# Sheet1.net
KiCad netlist of a schematic drawn in Altium Designer
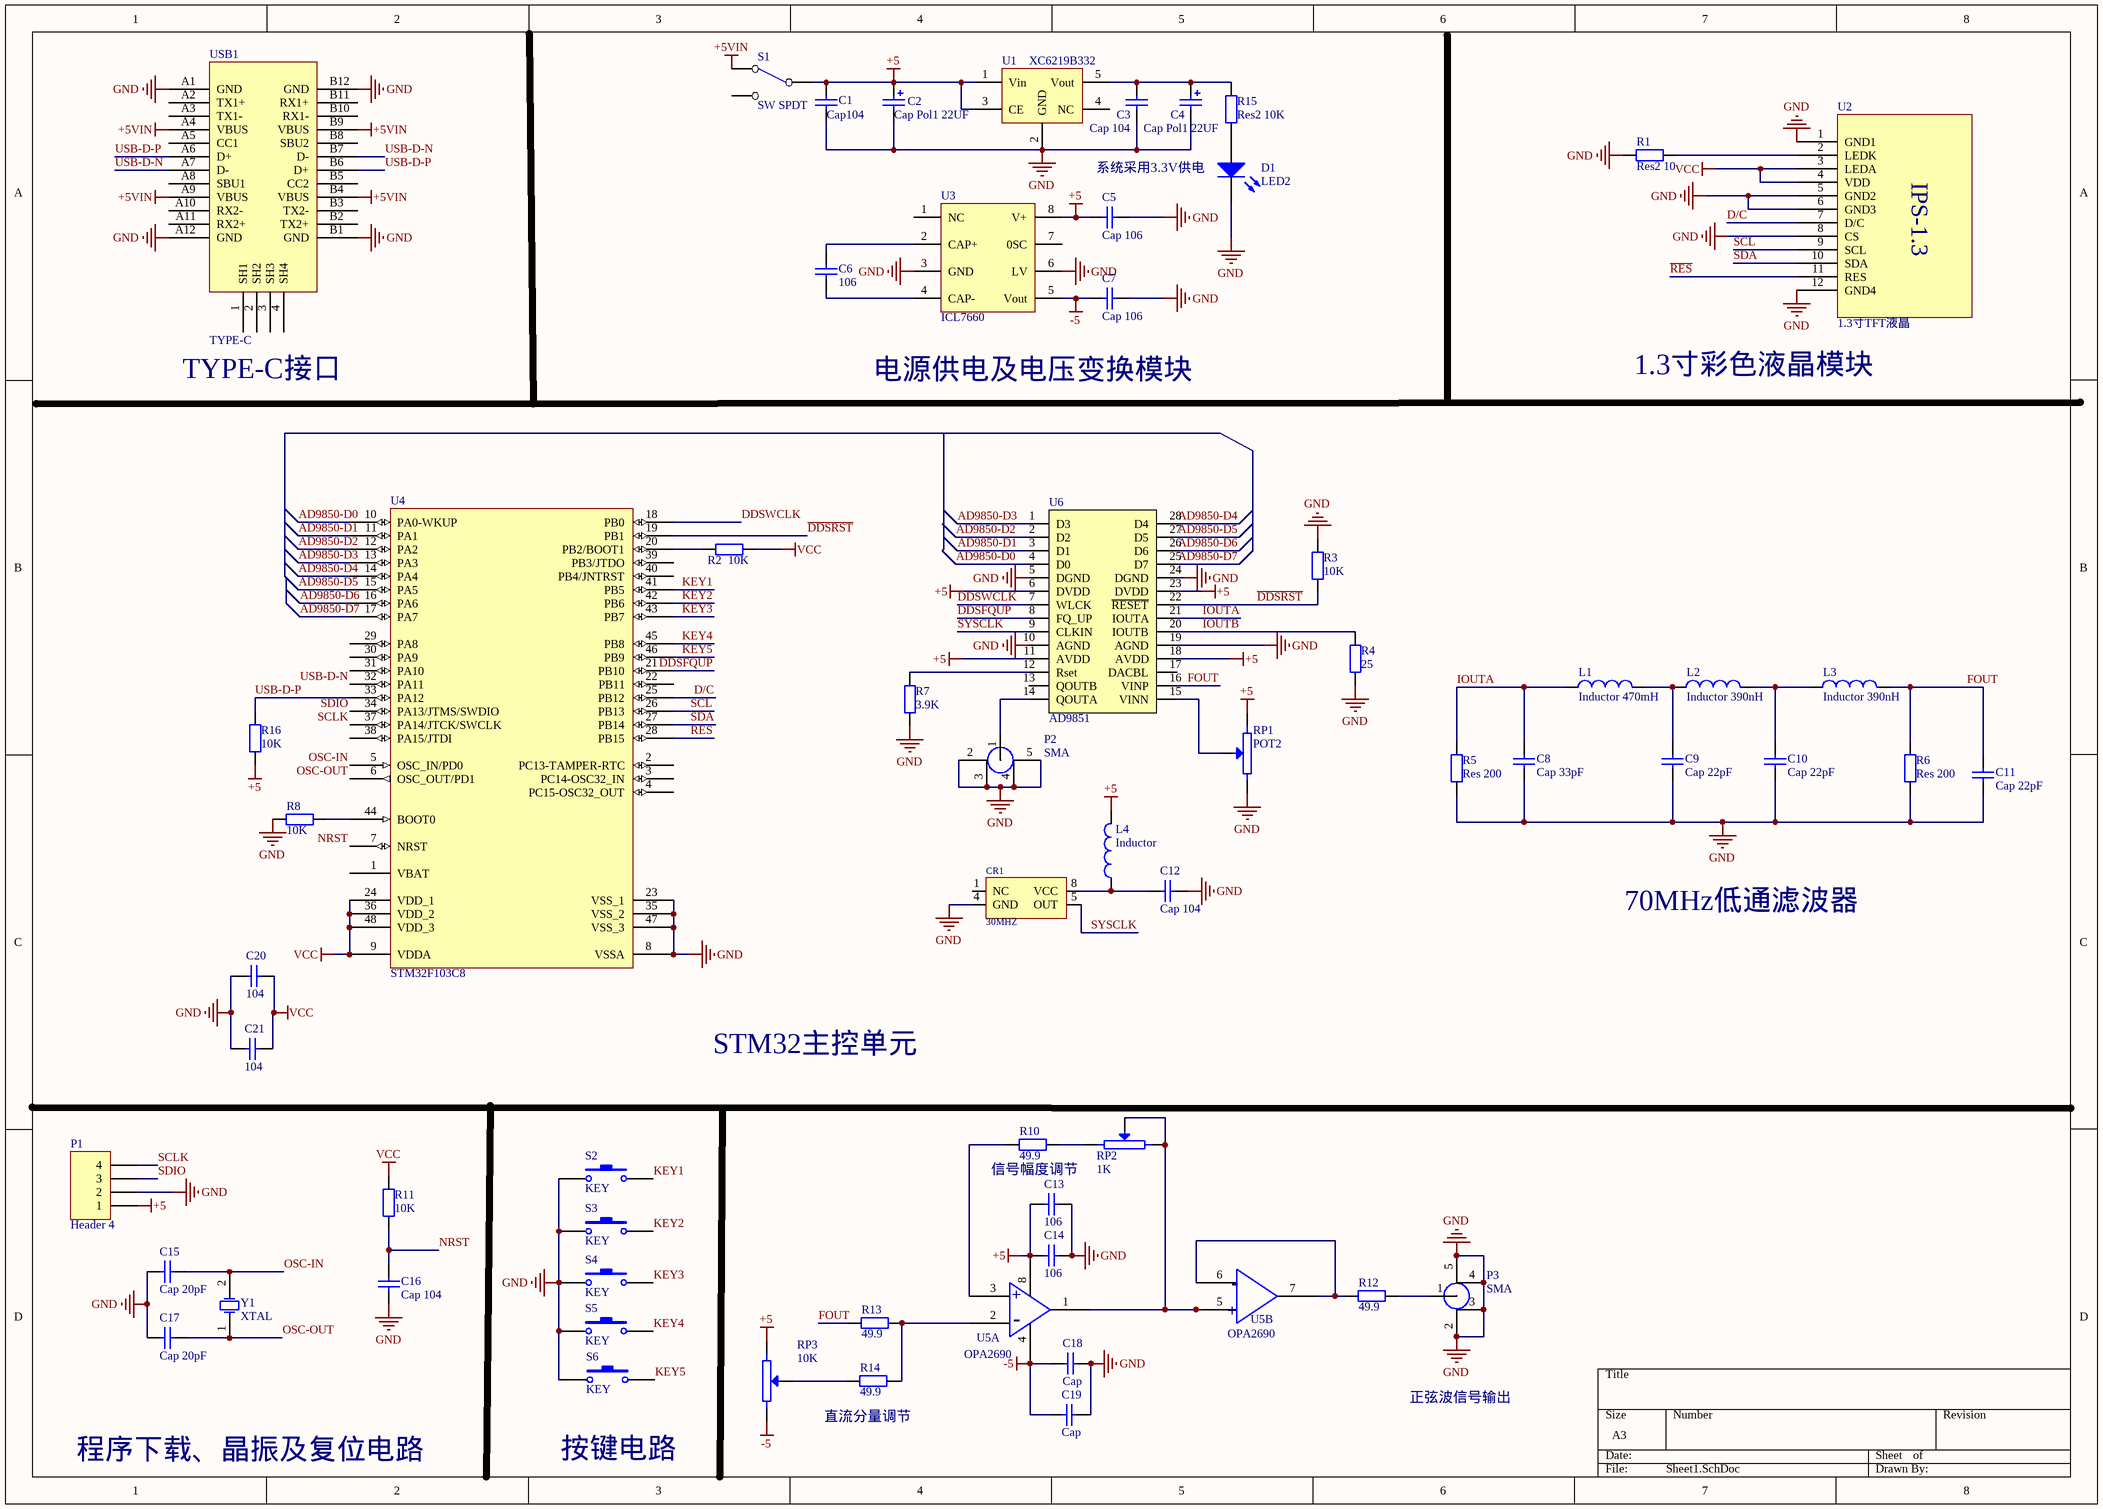
[diagram p0: Sheet1.SchDoc]

(export (version "E")
  (design (tool "Eeschema 10.0.6"))
  (components
    (comp (ref "C1")
      (value "Cap104")
      (footprint "C0805")
      (description "Capacitor")
      (fields (field (name "PUBLISHER") "Altium Limited"))
      (libsource (lib "基于STM32的DDS信号源设计实例") (part "Cap"))
    )
    (comp (ref "C2")
      (value "Cap Pol1 22UF")
      (footprint "C1210_N")
      (description "Polarized Capacitor (Radial)")
      (fields (field (name "PUBLISHER") "Altium Limited"))
      (libsource (lib "基于STM32的DDS信号源设计实例") (part "Cap Pol1"))
    )
    (comp (ref "C3")
      (value "Cap 104")
      (footprint "C0805")
      (description "Capacitor")
      (fields (field (name "PUBLISHER") "Altium Limited"))
      (libsource (lib "基于STM32的DDS信号源设计实例") (part "Cap"))
    )
    (comp (ref "C4")
      (value "Cap Pol1 22UF")
      (footprint "C1210_N")
      (description "Polarized Capacitor (Radial)")
      (fields (field (name "PUBLISHER") "Altium Limited"))
      (libsource (lib "基于STM32的DDS信号源设计实例") (part "Cap Pol1"))
    )
    (comp (ref "C5")
      (value "Cap 106")
      (footprint "C0805")
      (description "106")
      (fields (field (name "PUBLISHER") "Altium Limited"))
      (libsource (lib "基于STM32的DDS信号源设计实例") (part "Cap"))
    )
    (comp (ref "C6")
      (value "106")
      (footprint "C0805")
      (description "Capacitor")
      (fields (field (name "PUBLISHER") "Altium Limited"))
      (libsource (lib "基于STM32的DDS信号源设计实例") (part "Cap"))
    )
    (comp (ref "C7")
      (value "Cap 106")
      (footprint "C0805")
      (description "Capacitor")
      (fields (field (name "PUBLISHER") "Altium Limited"))
      (libsource (lib "基于STM32的DDS信号源设计实例") (part "Cap"))
    )
    (comp (ref "C8")
      (value "Cap 33pF")
      (footprint "C0805")
      (description "Capacitor")
      (fields (field (name "PUBLISHER") "Altium Limited"))
      (libsource (lib "基于STM32的DDS信号源设计实例") (part "Cap"))
    )
    (comp (ref "C9")
      (value "Cap 22pF")
      (footprint "C0805")
      (description "Capacitor")
      (fields (field (name "PUBLISHER") "Altium Limited"))
      (libsource (lib "基于STM32的DDS信号源设计实例") (part "Cap"))
    )
    (comp (ref "C10")
      (value "Cap 22pF")
      (footprint "C0805")
      (description "Capacitor")
      (fields (field (name "PUBLISHER") "Altium Limited"))
      (libsource (lib "基于STM32的DDS信号源设计实例") (part "Cap"))
    )
    (comp (ref "C11")
      (value "Cap 22pF")
      (footprint "C0805")
      (description "Capacitor")
      (fields (field (name "PUBLISHER") "Altium Limited"))
      (libsource (lib "基于STM32的DDS信号源设计实例") (part "Cap"))
    )
    (comp (ref "C12")
      (value "Cap 104")
      (footprint "C0805")
      (description "Capacitor")
      (fields (field (name "PUBLISHER") "Altium Limited"))
      (libsource (lib "基于STM32的DDS信号源设计实例") (part "Cap"))
    )
    (comp (ref "C13")
      (value "106")
      (footprint "C0805")
      (description "Capacitor")
      (fields (field (name "PUBLISHER") "Altium Limited"))
      (libsource (lib "基于STM32的DDS信号源设计实例") (part "Cap"))
    )
    (comp (ref "C14")
      (value "106")
      (footprint "C0805")
      (description "Capacitor")
      (fields (field (name "PUBLISHER") "Altium Limited"))
      (libsource (lib "基于STM32的DDS信号源设计实例") (part "Cap"))
    )
    (comp (ref "C15")
      (value "Cap 20pF")
      (footprint "C0805")
      (description "Capacitor")
      (fields (field (name "PUBLISHER") "Altium Limited"))
      (libsource (lib "基于STM32的DDS信号源设计实例") (part "Cap"))
    )
    (comp (ref "C16")
      (value "Cap 104")
      (footprint "C0805")
      (description "Capacitor")
      (fields (field (name "PUBLISHER") "Altium Limited"))
      (libsource (lib "基于STM32的DDS信号源设计实例") (part "Cap"))
    )
    (comp (ref "C17")
      (value "Cap 20pF")
      (footprint "C0805")
      (description "Capacitor")
      (fields (field (name "PUBLISHER") "Altium Limited"))
      (libsource (lib "基于STM32的DDS信号源设计实例") (part "Cap"))
    )
    (comp (ref "C18")
      (value "Cap")
      (footprint "C0805")
      (description "Capacitor")
      (fields (field (name "PUBLISHER") "Altium Limited"))
      (libsource (lib "基于STM32的DDS信号源设计实例") (part "Cap"))
    )
    (comp (ref "C19")
      (value "Cap")
      (footprint "C0805")
      (description "Capacitor")
      (fields (field (name "PUBLISHER") "Altium Limited"))
      (libsource (lib "基于STM32的DDS信号源设计实例") (part "Cap"))
    )
    (comp (ref "C20")
      (value "104")
      (footprint "C0805")
      (description "Capacitor")
      (fields (field (name "PUBLISHER") "Altium Limited"))
      (libsource (lib "基于STM32的DDS信号源设计实例") (part "Cap"))
    )
    (comp (ref "C21")
      (value "104")
      (footprint "C0805")
      (description "Capacitor")
      (fields (field (name "PUBLISHER") "Altium Limited"))
      (libsource (lib "基于STM32的DDS信号源设计实例") (part "Cap"))
    )
    (comp (ref "CR1")
      (value "30MHZ")
      (footprint "CRYSTAL-SMT-5X7")
      (libsource (lib "基于STM32的DDS信号源设计实例") (part "CRYSTAL-DIP8"))
    )
    (comp (ref "D1")
      (value "LED2")
      (footprint "D0805+")
      (description "Typical RED, GREEN, YELLOW, AMBER GaAs LED")
      (fields (field (name "PUBLISHER") "Altium Limited"))
      (libsource (lib "基于STM32的DDS信号源设计实例") (part "LED2"))
    )
    (comp (ref "L1")
      (value "Inductor 470mH")
      (footprint "6-0805_N")
      (description "Inductor")
      (fields (field (name "PUBLISHER") "Altium Limited"))
      (libsource (lib "基于STM32的DDS信号源设计实例") (part "Inductor"))
    )
    (comp (ref "L2")
      (value "Inductor 390nH")
      (footprint "6-0805_N")
      (description "Inductor")
      (fields (field (name "PUBLISHER") "Altium Limited"))
      (libsource (lib "基于STM32的DDS信号源设计实例") (part "Inductor"))
    )
    (comp (ref "L3")
      (value "Inductor 390nH")
      (footprint "6-0805_N")
      (description "Inductor")
      (fields (field (name "PUBLISHER") "Altium Limited"))
      (libsource (lib "基于STM32的DDS信号源设计实例") (part "Inductor"))
    )
    (comp (ref "L4")
      (value "Inductor")
      (footprint "6-0805_N")
      (fields (field (name "PUBLISHER") "Altium Limited"))
      (libsource (lib "基于STM32的DDS信号源设计实例") (part "Inductor"))
    )
    (comp (ref "P1")
      (value "Header 4")
      (footprint "HDR1X4")
      (description "Header, 4-Pin")
      (fields (field (name "PUBLISHER") "Altium Limited"))
      (libsource (lib "基于STM32的DDS信号源设计实例") (part "Header 4"))
    )
    (comp (ref "P2") (value "SMA") (footprint "SMA-KE") (libsource (lib "Schlib1") (part "SMA")))
    (comp (ref "P3") (value "SMA") (footprint "SMA-KE") (libsource (lib "Schlib1") (part "SMA")))
    (comp (ref "R1")
      (value "Res2 10")
      (footprint "6-0805_N")
      (description "Resistor")
      (fields (field (name "PUBLISHER") "Altium Limited"))
      (libsource (lib "") (part "Res2_1"))
    )
    (comp (ref "R2")
      (value "10K")
      (footprint "6-0805_N")
      (description "Resistor")
      (fields (field (name "PUBLISHER") "Altium Limited"))
      (libsource (lib "") (part "Res2_1"))
    )
    (comp (ref "R3")
      (value "10K")
      (footprint "6-0805_N")
      (description "Resistor")
      (fields (field (name "PUBLISHER") "Altium Limited"))
      (libsource (lib "基于STM32的DDS信号源设计实例") (part "Res2"))
    )
    (comp (ref "R4")
      (value "25")
      (footprint "6-0805_N")
      (description "Resistor")
      (fields (field (name "PUBLISHER") "Altium Limited"))
      (libsource (lib "基于STM32的DDS信号源设计实例") (part "Res2"))
    )
    (comp (ref "R5")
      (value "Res 200")
      (footprint "6-0805_N")
      (description "Resistor")
      (fields (field (name "PUBLISHER") "Altium Limited"))
      (libsource (lib "基于STM32的DDS信号源设计实例") (part "Res2"))
    )
    (comp (ref "R6")
      (value "Res 200")
      (footprint "6-0805_N")
      (description "Resistor")
      (fields (field (name "PUBLISHER") "Altium Limited"))
      (libsource (lib "基于STM32的DDS信号源设计实例") (part "Res2"))
    )
    (comp (ref "R7")
      (value "3.9K")
      (footprint "6-0805_N")
      (description "Resistor")
      (fields (field (name "PUBLISHER") "Altium Limited"))
      (libsource (lib "基于STM32的DDS信号源设计实例") (part "Res2"))
    )
    (comp (ref "R8")
      (value "10K")
      (footprint "6-0805_N")
      (description "Resistor")
      (fields (field (name "PUBLISHER") "Altium Limited"))
      (libsource (lib "") (part "Res2_1"))
    )
    (comp (ref "R10")
      (value "49.9")
      (footprint "6-0805_N")
      (description "Resistor")
      (fields (field (name "PUBLISHER") "Altium Limited"))
      (libsource (lib "") (part "Res2_1"))
    )
    (comp (ref "R11")
      (value "10K")
      (footprint "6-0805_N")
      (description "Resistor")
      (fields (field (name "PUBLISHER") "Altium Limited"))
      (libsource (lib "基于STM32的DDS信号源设计实例") (part "Res2"))
    )
    (comp (ref "R12")
      (value "49.9")
      (footprint "6-0805_N")
      (description "Resistor")
      (fields (field (name "PUBLISHER") "Altium Limited"))
      (libsource (lib "") (part "Res2_1"))
    )
    (comp (ref "R13")
      (value "49.9")
      (footprint "6-0805_N")
      (description "Resistor")
      (fields (field (name "PUBLISHER") "Altium Limited"))
      (libsource (lib "") (part "Res2_1"))
    )
    (comp (ref "R14")
      (value "49.9")
      (footprint "6-0805_N")
      (description "Resistor")
      (fields (field (name "PUBLISHER") "Altium Limited"))
      (libsource (lib "") (part "Res2_1"))
    )
    (comp (ref "R15")
      (value "Res2 10K")
      (footprint "6-0805_N")
      (description "Resistor")
      (fields (field (name "PUBLISHER") "Altium Limited"))
      (libsource (lib "基于STM32的DDS信号源设计实例") (part "Res2"))
    )
    (comp (ref "R16")
      (value "10K")
      (footprint "6-0805_N")
      (description "Resistor")
      (fields (field (name "PUBLISHER") "Altium Limited"))
      (libsource (lib "基于STM32的DDS信号源设计实例") (part "Res2"))
    )
    (comp (ref "RP1")
      (value "POT2")
      (footprint "VR7")
      (description "Potentiometer")
      (libsource (lib "基于STM32的DDS信号源设计实例") (part "POT2"))
    )
    (comp (ref "RP2")
      (value "1K")
      (footprint "VR7")
      (description "Potentiometer")
      (libsource (lib "基于STM32的DDS信号源设计实例") (part "POT2"))
    )
    (comp (ref "RP3")
      (value "10K")
      (footprint "VR7")
      (description "Potentiometer")
      (libsource (lib "基于STM32的DDS信号源设计实例") (part "POT2"))
    )
    (comp (ref "S1")
      (value "SW SPDT")
      (footprint "SW-SPDT-7P")
      (libsource (lib "基于STM32的DDS信号源设计实例") (part "SW SPDT"))
    )
    (comp (ref "S2")
      (value "KEY")
      (footprint "SW-MINI")
      (description "Switch")
      (fields (field (name "PUBLISHER") "Altium Limited"))
      (libsource (lib "基于STM32的DDS信号源设计实例") (part "SW-PB"))
    )
    (comp (ref "S3")
      (value "KEY")
      (footprint "SW-MINI")
      (description "Switch")
      (fields (field (name "PUBLISHER") "Altium Limited"))
      (libsource (lib "基于STM32的DDS信号源设计实例") (part "SW-PB"))
    )
    (comp (ref "S4")
      (value "KEY")
      (footprint "SW-MINI")
      (description "Switch")
      (fields (field (name "PUBLISHER") "Altium Limited"))
      (libsource (lib "基于STM32的DDS信号源设计实例") (part "SW-PB"))
    )
    (comp (ref "S5")
      (value "KEY")
      (footprint "SW-MINI")
      (description "Switch")
      (fields (field (name "PUBLISHER") "Altium Limited"))
      (libsource (lib "基于STM32的DDS信号源设计实例") (part "SW-PB"))
    )
    (comp (ref "S6")
      (value "KEY")
      (footprint "SW-MINI")
      (description "Switch")
      (fields (field (name "PUBLISHER") "Altium Limited"))
      (libsource (lib "基于STM32的DDS信号源设计实例") (part "SW-PB"))
    )
    (comp (ref "U1")
      (value "XC6219B332")
      (footprint "SOT23-5L")
      (libsource (lib "基于STM32的DDS信号源设计实例") (part "XC6219"))
    )
    (comp (ref "U2")
      (value "1.3寸TFT液晶")
      (footprint "1.3-TFT-TPS")
      (libsource (lib "基于STM32的DDS信号源设计实例") (part "1.3寸TFT液晶"))
    )
    (comp (ref "U3")
      (value "ICL7660")
      (footprint "SO8_N")
      (libsource (lib "基于STM32的DDS信号源设计实例") (part "ICL7660"))
    )
    (comp (ref "U4")
      (value "STM32F103C8")
      (footprint "TQFP-48")
      (description "Flaah:64/RAM:20/IO:36")
      (fields (field (name "版权归属") "源创客"))
      (libsource (lib "基于STM32的DDS信号源设计实例") (part "STM32F103C8"))
    )
    (comp (ref "U5") (value "OPA2690") (footprint "SO-8") (libsource (lib "Schlib1") (part "OPA2690")))
    (comp (ref "U6") (value "AD9851") (footprint "TSSOP28") (libsource (lib "Schlib1") (part "AD9851")))
    (comp (ref "USB1")
      (value "TYPE-C")
      (footprint "TYPE-C")
      (libsource (lib "基于STM32的DDS信号源设计实例") (part "TYPE-C"))
    )
    (comp (ref "Y1")
      (value "XTAL")
      (footprint "XTAL2")
      (description "Crystal Oscillator")
      (fields (field (name "PUBLISHER") "Altium Limited"))
      (libsource (lib "基于STM32的DDS信号源设计实例") (part "XTAL"))
    )
  )
  (nets
    (net (code "1") (name "+5") (class "Default")
      (node (ref "C1") (pin "2") (pinfunction "2_2") (pintype "passive"))
      (node (ref "C13") (pin "1") (pinfunction "1_1") (pintype "passive"))
      (node (ref "C14") (pin "1") (pinfunction "1_1") (pintype "passive"))
      (node (ref "C2") (pin "1") (pinfunction "1_1") (pintype "passive"))
      (node (ref "C5") (pin "2") (pinfunction "2_2") (pintype "passive"))
      (node (ref "L4") (pin "2") (pinfunction "2_2") (pintype "passive"))
      (node (ref "P1") (pin "1") (pinfunction "1_1") (pintype "passive"))
      (node (ref "R16") (pin "1") (pinfunction "1_1") (pintype "passive"))
      (node (ref "RP1") (pin "2") (pinfunction "2_2") (pintype "passive"))
      (node (ref "RP3") (pin "1") (pinfunction "1_1") (pintype "passive"))
      (node (ref "S1") (pin "2") (pinfunction "COMMON_2") (pintype "passive"))
      (node (ref "U1") (pin "1") (pinfunction "Vin_1") (pintype "passive"))
      (node (ref "U1") (pin "3") (pinfunction "CE_3") (pintype "passive"))
      (node (ref "U3") (pin "8") (pinfunction "V+_8") (pintype "passive"))
      (node (ref "U5") (pin "8") (pintype "passive"))
      (node (ref "U6") (pin "11") (pinfunction "AVDD_11") (pintype "passive"))
      (node (ref "U6") (pin "18") (pinfunction "AVDD_18") (pintype "passive"))
      (node (ref "U6") (pin "23") (pinfunction "DVDD_23") (pintype "passive"))
      (node (ref "U6") (pin "6") (pinfunction "DVDD_6") (pintype "passive"))
    )
    (net (code "2") (name "+5VIN") (class "Default")
      (node (ref "S1") (pin "1") (pinfunction "NC_1") (pintype "passive"))
      (node (ref "USB1") (pin "A4") (pinfunction "VBUS_A4") (pintype "passive"))
      (node (ref "USB1") (pin "A9") (pinfunction "VBUS_A9") (pintype "passive"))
      (node (ref "USB1") (pin "B4") (pinfunction "VBUS_B4") (pintype "passive"))
      (node (ref "USB1") (pin "B9") (pinfunction "VBUS_B9") (pintype "passive"))
    )
    (net (code "3") (name "-5") (class "Default")
      (node (ref "C18") (pin "1") (pinfunction "1_1") (pintype "passive"))
      (node (ref "C19") (pin "1") (pinfunction "1_1") (pintype "passive"))
      (node (ref "C7") (pin "2") (pinfunction "2_2") (pintype "passive"))
      (node (ref "RP3") (pin "2") (pinfunction "2_2") (pintype "passive"))
      (node (ref "U3") (pin "5") (pinfunction "Vout_5") (pintype "passive"))
      (node (ref "U5") (pin "4") (pintype "passive"))
    )
    (net (code "4") (name "/AD9850-D0") (class "Default")
      (node (ref "U4") (pin "10") (pinfunction "PA0-WKUP_10") (pintype "bidirectional"))
      (node (ref "U6") (pin "4") (pinfunction "D0_4") (pintype "passive"))
    )
    (net (code "5") (name "/AD9850-D1") (class "Default")
      (node (ref "U4") (pin "11") (pinfunction "PA1_11") (pintype "bidirectional"))
      (node (ref "U6") (pin "3") (pinfunction "D1_3") (pintype "passive"))
    )
    (net (code "6") (name "/AD9850-D2") (class "Default")
      (node (ref "U4") (pin "12") (pinfunction "PA2_12") (pintype "bidirectional"))
      (node (ref "U6") (pin "2") (pinfunction "D2_2") (pintype "passive"))
    )
    (net (code "7") (name "/AD9850-D3") (class "Default")
      (node (ref "U4") (pin "13") (pinfunction "PA3_13") (pintype "bidirectional"))
      (node (ref "U6") (pin "1") (pinfunction "D3_1") (pintype "passive"))
    )
    (net (code "8") (name "/AD9850-D4") (class "Default")
      (node (ref "U4") (pin "14") (pinfunction "PA4_14") (pintype "bidirectional"))
      (node (ref "U6") (pin "28") (pinfunction "D4_28") (pintype "passive"))
    )
    (net (code "9") (name "/AD9850-D5") (class "Default")
      (node (ref "U4") (pin "15") (pinfunction "PA5_15") (pintype "bidirectional"))
      (node (ref "U6") (pin "27") (pinfunction "D5_27") (pintype "passive"))
    )
    (net (code "10") (name "/AD9850-D6") (class "Default")
      (node (ref "U4") (pin "16") (pinfunction "PA6_16") (pintype "bidirectional"))
      (node (ref "U6") (pin "26") (pinfunction "D6_26") (pintype "passive"))
    )
    (net (code "11") (name "/AD9850-D7") (class "Default")
      (node (ref "U4") (pin "17") (pinfunction "PA7_17") (pintype "bidirectional"))
      (node (ref "U6") (pin "25") (pinfunction "D7_25") (pintype "passive"))
    )
    (net (code "12") (name "/DDSFQUP") (class "Default")
      (node (ref "U4") (pin "21") (pinfunction "PB10_21") (pintype "bidirectional"))
      (node (ref "U6") (pin "8") (pinfunction "FQ_UP_8") (pintype "passive"))
    )
    (net (code "13") (name "/DDSWCLK") (class "Default")
      (node (ref "U4") (pin "18") (pinfunction "PB0_18") (pintype "bidirectional"))
      (node (ref "U6") (pin "7") (pinfunction "WLCK_7") (pintype "passive"))
    )
    (net (code "14") (name "/D{slash}C") (class "Default")
      (node (ref "U2") (pin "7") (pinfunction "D/C_7") (pintype "passive"))
      (node (ref "U4") (pin "25") (pinfunction "PB12_25") (pintype "bidirectional"))
    )
    (net (code "15") (name "/FOUT") (class "Default")
      (node (ref "C11") (pin "2") (pinfunction "2_2") (pintype "passive"))
      (node (ref "L3") (pin "2") (pinfunction "2_2") (pintype "passive"))
      (node (ref "R13") (pin "1") (pinfunction "1_1") (pintype "passive"))
      (node (ref "R6") (pin "2") (pinfunction "2_2") (pintype "passive"))
      (node (ref "U6") (pin "16") (pinfunction "VINP_16") (pintype "passive"))
    )
    (net (code "16") (name "/IOUTA") (class "Default")
      (node (ref "C8") (pin "2") (pinfunction "2_2") (pintype "passive"))
      (node (ref "L1") (pin "1") (pinfunction "1_1") (pintype "passive"))
      (node (ref "R5") (pin "2") (pinfunction "2_2") (pintype "passive"))
      (node (ref "U6") (pin "21") (pinfunction "IOUTA_21") (pintype "passive"))
    )
    (net (code "17") (name "/IOUTB") (class "Default")
      (node (ref "R4") (pin "2") (pinfunction "2_2") (pintype "passive"))
      (node (ref "U6") (pin "20") (pinfunction "IOUTB_20") (pintype "passive"))
    )
    (net (code "18") (name "/KEY1") (class "Default")
      (node (ref "S2") (pin "2") (pinfunction "2_2") (pintype "passive"))
      (node (ref "U4") (pin "41") (pinfunction "PB5_41") (pintype "bidirectional"))
    )
    (net (code "19") (name "/KEY2") (class "Default")
      (node (ref "S3") (pin "2") (pinfunction "2_2") (pintype "passive"))
      (node (ref "U4") (pin "42") (pinfunction "PB6_42") (pintype "bidirectional"))
    )
    (net (code "20") (name "/KEY3") (class "Default")
      (node (ref "S4") (pin "2") (pinfunction "2_2") (pintype "passive"))
      (node (ref "U4") (pin "43") (pinfunction "PB7_43") (pintype "bidirectional"))
    )
    (net (code "21") (name "/KEY4") (class "Default")
      (node (ref "S5") (pin "2") (pinfunction "2_2") (pintype "passive"))
      (node (ref "U4") (pin "45") (pinfunction "PB8_45") (pintype "bidirectional"))
    )
    (net (code "22") (name "/KEY5") (class "Default")
      (node (ref "S6") (pin "2") (pinfunction "2_2") (pintype "passive"))
      (node (ref "U4") (pin "46") (pinfunction "PB9_46") (pintype "bidirectional"))
    )
    (net (code "23") (name "/NRST") (class "Default")
      (node (ref "C16") (pin "2") (pinfunction "2_2") (pintype "passive"))
      (node (ref "R11") (pin "1") (pinfunction "1_1") (pintype "passive"))
      (node (ref "U4") (pin "7") (pinfunction "NRST_7") (pintype "bidirectional"))
    )
    (net (code "24") (name "/OSC-IN") (class "Default")
      (node (ref "C15") (pin "2") (pinfunction "2_2") (pintype "passive"))
      (node (ref "U4") (pin "5") (pinfunction "OSC_IN/PD0_5") (pintype "input"))
      (node (ref "Y1") (pin "2") (pinfunction "OSC2_2") (pintype "passive"))
    )
    (net (code "25") (name "/OSC-OUT") (class "Default")
      (node (ref "C17") (pin "2") (pinfunction "2_2") (pintype "passive"))
      (node (ref "U4") (pin "6") (pinfunction "OSC_OUT/PD1_6") (pintype "output"))
      (node (ref "Y1") (pin "1") (pinfunction "OSC1_1") (pintype "passive"))
    )
    (net (code "26") (name "/SCL") (class "Default")
      (node (ref "U2") (pin "9") (pinfunction "SCL_9") (pintype "passive"))
      (node (ref "U4") (pin "26") (pinfunction "PB13_26") (pintype "bidirectional"))
    )
    (net (code "27") (name "/SCLK") (class "Default")
      (node (ref "P1") (pin "4") (pinfunction "4_4") (pintype "passive"))
      (node (ref "U4") (pin "37") (pinfunction "PA14/JTCK/SWCLK_37") (pintype "bidirectional"))
    )
    (net (code "28") (name "/SDA") (class "Default")
      (node (ref "U2") (pin "10") (pinfunction "SDA_10") (pintype "passive"))
      (node (ref "U4") (pin "27") (pinfunction "PB14_27") (pintype "bidirectional"))
    )
    (net (code "29") (name "/SDIO") (class "Default")
      (node (ref "P1") (pin "3") (pinfunction "3_3") (pintype "passive"))
      (node (ref "U4") (pin "34") (pinfunction "PA13/JTMS/SWDIO_34") (pintype "bidirectional"))
    )
    (net (code "30") (name "/SYSCLK") (class "Default")
      (node (ref "CR1") (pin "5") (pinfunction "OUT_5") (pintype "passive"))
      (node (ref "U6") (pin "9") (pinfunction "CLKIN_9") (pintype "passive"))
    )
    (net (code "31") (name "/USB-D-N") (class "Default")
      (node (ref "U4") (pin "32") (pinfunction "PA11_32") (pintype "bidirectional"))
      (node (ref "USB1") (pin "A7") (pinfunction "D-_A7") (pintype "passive"))
      (node (ref "USB1") (pin "B7") (pinfunction "D-_B7") (pintype "passive"))
    )
    (net (code "32") (name "/USB-D-P") (class "Default")
      (node (ref "R16") (pin "2") (pinfunction "2_2") (pintype "passive"))
      (node (ref "U4") (pin "33") (pinfunction "PA12_33") (pintype "bidirectional"))
      (node (ref "USB1") (pin "A6") (pinfunction "D+_A6") (pintype "passive"))
      (node (ref "USB1") (pin "B6") (pinfunction "D+_B6") (pintype "passive"))
    )
    (net (code "33") (name "/~{DDSRST}") (class "Default")
      (node (ref "R3") (pin "1") (pinfunction "1_1") (pintype "passive"))
      (node (ref "U4") (pin "19") (pinfunction "PB1_19") (pintype "bidirectional"))
      (node (ref "U6") (pin "22") (pinfunction "~{RESET}_22") (pintype "passive"))
    )
    (net (code "34") (name "/~{RES}") (class "Default")
      (node (ref "U2") (pin "11") (pinfunction "RES_11") (pintype "passive"))
      (node (ref "U4") (pin "28") (pinfunction "PB15_28") (pintype "bidirectional"))
    )
    (net (code "35") (name "GND") (class "Default")
      (node (ref "C1") (pin "1") (pinfunction "1_1") (pintype "passive"))
      (node (ref "C10") (pin "1") (pinfunction "1_1") (pintype "passive"))
      (node (ref "C11") (pin "1") (pinfunction "1_1") (pintype "passive"))
      (node (ref "C12") (pin "2") (pinfunction "2_2") (pintype "passive"))
      (node (ref "C13") (pin "2") (pinfunction "2_2") (pintype "passive"))
      (node (ref "C14") (pin "2") (pinfunction "2_2") (pintype "passive"))
      (node (ref "C15") (pin "1") (pinfunction "1_1") (pintype "passive"))
      (node (ref "C16") (pin "1") (pinfunction "1_1") (pintype "passive"))
      (node (ref "C17") (pin "1") (pinfunction "1_1") (pintype "passive"))
      (node (ref "C18") (pin "2") (pinfunction "2_2") (pintype "passive"))
      (node (ref "C19") (pin "2") (pinfunction "2_2") (pintype "passive"))
      (node (ref "C2") (pin "2") (pinfunction "2_2") (pintype "passive"))
      (node (ref "C20") (pin "1") (pinfunction "1_1") (pintype "passive"))
      (node (ref "C21") (pin "1") (pinfunction "1_1") (pintype "passive"))
      (node (ref "C3") (pin "1") (pinfunction "1_1") (pintype "passive"))
      (node (ref "C4") (pin "2") (pinfunction "2_2") (pintype "passive"))
      (node (ref "C5") (pin "1") (pinfunction "1_1") (pintype "passive"))
      (node (ref "C7") (pin "1") (pinfunction "1_1") (pintype "passive"))
      (node (ref "C8") (pin "1") (pinfunction "1_1") (pintype "passive"))
      (node (ref "C9") (pin "1") (pinfunction "1_1") (pintype "passive"))
      (node (ref "CR1") (pin "4") (pinfunction "GND_4") (pintype "passive"))
      (node (ref "D1") (pin "K") (pinfunction "K_K") (pintype "passive"))
      (node (ref "P1") (pin "2") (pinfunction "2_2") (pintype "passive"))
      (node (ref "P2") (pin "2") (pintype "passive"))
      (node (ref "P2") (pin "3") (pintype "passive"))
      (node (ref "P2") (pin "4") (pintype "passive"))
      (node (ref "P2") (pin "5") (pintype "passive"))
      (node (ref "P3") (pin "2") (pintype "passive"))
      (node (ref "P3") (pin "3") (pintype "passive"))
      (node (ref "P3") (pin "4") (pintype "passive"))
      (node (ref "P3") (pin "5") (pintype "passive"))
      (node (ref "R1") (pin "1") (pinfunction "1_1") (pintype "passive"))
      (node (ref "R3") (pin "2") (pinfunction "2_2") (pintype "passive"))
      (node (ref "R4") (pin "1") (pinfunction "1_1") (pintype "passive"))
      (node (ref "R5") (pin "1") (pinfunction "1_1") (pintype "passive"))
      (node (ref "R6") (pin "1") (pinfunction "1_1") (pintype "passive"))
      (node (ref "R7") (pin "1") (pinfunction "1_1") (pintype "passive"))
      (node (ref "R8") (pin "1") (pinfunction "1_1") (pintype "passive"))
      (node (ref "RP1") (pin "1") (pinfunction "1_1") (pintype "passive"))
      (node (ref "S2") (pin "1") (pinfunction "1_1") (pintype "passive"))
      (node (ref "S3") (pin "1") (pinfunction "1_1") (pintype "passive"))
      (node (ref "S4") (pin "1") (pinfunction "1_1") (pintype "passive"))
      (node (ref "S5") (pin "1") (pinfunction "1_1") (pintype "passive"))
      (node (ref "S6") (pin "1") (pinfunction "1_1") (pintype "passive"))
      (node (ref "U1") (pin "2") (pinfunction "GND_2") (pintype "power_in"))
      (node (ref "U2") (pin "1") (pinfunction "GND1_1") (pintype "passive"))
      (node (ref "U2") (pin "12") (pinfunction "GND4_12") (pintype "passive"))
      (node (ref "U2") (pin "5") (pinfunction "GND2_5") (pintype "passive"))
      (node (ref "U2") (pin "6") (pinfunction "GND3_6") (pintype "passive"))
      (node (ref "U2") (pin "8") (pinfunction "CS_8") (pintype "passive"))
      (node (ref "U3") (pin "3") (pinfunction "GND_3") (pintype "passive"))
      (node (ref "U3") (pin "6") (pinfunction "LV_6") (pintype "passive"))
      (node (ref "U4") (pin "23") (pinfunction "VSS_1_23") (pintype "power_in"))
      (node (ref "U4") (pin "35") (pinfunction "VSS_2_35") (pintype "power_in"))
      (node (ref "U4") (pin "47") (pinfunction "VSS_3_47") (pintype "power_in"))
      (node (ref "U4") (pin "8") (pinfunction "VSSA_8") (pintype "power_in"))
      (node (ref "U6") (pin "10") (pinfunction "AGND_10") (pintype "passive"))
      (node (ref "U6") (pin "19") (pinfunction "AGND_19") (pintype "passive"))
      (node (ref "U6") (pin "24") (pinfunction "DGND_24") (pintype "passive"))
      (node (ref "U6") (pin "5") (pinfunction "DGND_5") (pintype "passive"))
      (node (ref "USB1") (pin "A1") (pinfunction "GND_A1") (pintype "passive"))
      (node (ref "USB1") (pin "A12") (pinfunction "GND_A12") (pintype "passive"))
      (node (ref "USB1") (pin "B1") (pinfunction "GND_B1") (pintype "passive"))
      (node (ref "USB1") (pin "B12") (pinfunction "GND_B12") (pintype "passive"))
    )
    (net (code "36") (name "Net-(C9-Pad2)") (class "Default")
      (node (ref "C9") (pin "2") (pinfunction "2_2") (pintype "passive"))
      (node (ref "L1") (pin "2") (pinfunction "2_2") (pintype "passive"))
      (node (ref "L2") (pin "1") (pinfunction "1_1") (pintype "passive"))
    )
    (net (code "37") (name "Net-(C10-Pad2)") (class "Default")
      (node (ref "C10") (pin "2") (pinfunction "2_2") (pintype "passive"))
      (node (ref "L2") (pin "2") (pinfunction "2_2") (pintype "passive"))
      (node (ref "L3") (pin "1") (pinfunction "1_1") (pintype "passive"))
    )
    (net (code "38") (name "Net-(CR1-VCC)") (class "Default")
      (node (ref "C12") (pin "1") (pinfunction "1_1") (pintype "passive"))
      (node (ref "CR1") (pin "8") (pinfunction "VCC_8") (pintype "passive"))
      (node (ref "L4") (pin "1") (pinfunction "1_1") (pintype "passive"))
    )
    (net (code "39") (name "Net-(D1-PadA)") (class "Default")
      (node (ref "D1") (pin "A") (pinfunction "A_A") (pintype "passive"))
      (node (ref "R15") (pin "1") (pinfunction "1_1") (pintype "passive"))
    )
    (net (code "40") (name "Net-(P3-Pad1)") (class "Default")
      (node (ref "P3") (pin "1") (pintype "passive"))
      (node (ref "R12") (pin "2") (pinfunction "2_2") (pintype "passive"))
    )
    (net (code "41") (name "Net-(R10-Pad1)") (class "Default")
      (node (ref "R10") (pin "1") (pinfunction "1_1") (pintype "passive"))
      (node (ref "U5") (pin "3") (pintype "passive"))
    )
    (net (code "42") (name "Net-(R10-Pad2)") (class "Default")
      (node (ref "R10") (pin "2") (pinfunction "2_2") (pintype "passive"))
      (node (ref "RP2") (pin "1") (pinfunction "1_1") (pintype "passive"))
    )
    (net (code "43") (name "Net-(R12-Pad1)") (class "Default")
      (node (ref "R12") (pin "1") (pinfunction "1_1") (pintype "passive"))
      (node (ref "U5") (pin "6") (pintype "passive"))
      (node (ref "U5") (pin "7") (pintype "passive"))
    )
    (net (code "44") (name "Net-(R13-Pad2)") (class "Default")
      (node (ref "R13") (pin "2") (pinfunction "2_2") (pintype "passive"))
      (node (ref "R14") (pin "2") (pinfunction "2_2") (pintype "passive"))
      (node (ref "U5") (pin "2") (pintype "passive"))
    )
    (net (code "45") (name "Net-(R14-Pad1)") (class "Default")
      (node (ref "R14") (pin "1") (pinfunction "1_1") (pintype "passive"))
      (node (ref "RP3") (pin "3") (pinfunction "3_3") (pintype "passive"))
    )
    (net (code "46") (name "Net-(RP2-Pad2)") (class "Default")
      (node (ref "RP2") (pin "2") (pinfunction "2_2") (pintype "passive"))
      (node (ref "RP2") (pin "3") (pinfunction "3_3") (pintype "passive"))
      (node (ref "U5") (pin "1") (pintype "passive"))
      (node (ref "U5") (pin "5") (pintype "passive"))
    )
    (net (code "47") (name "Net-(U1-Vout)") (class "Default")
      (node (ref "C3") (pin "2") (pinfunction "2_2") (pintype "passive"))
      (node (ref "C4") (pin "1") (pinfunction "1_1") (pintype "passive"))
      (node (ref "R15") (pin "2") (pinfunction "2_2") (pintype "passive"))
      (node (ref "U1") (pin "5") (pinfunction "Vout_5") (pintype "passive"))
    )
    (net (code "48") (name "Net-(U2-LEDK)") (class "Default")
      (node (ref "R1") (pin "2") (pinfunction "2_2") (pintype "passive"))
      (node (ref "U2") (pin "2") (pinfunction "LEDK_2") (pintype "passive"))
    )
    (net (code "49") (name "Net-(U3-CAP+)") (class "Default")
      (node (ref "C6") (pin "2") (pinfunction "2_2") (pintype "passive"))
      (node (ref "U3") (pin "2") (pinfunction "CAP+_2") (pintype "passive"))
    )
    (net (code "50") (name "Net-(U3-CAP-)") (class "Default")
      (node (ref "C6") (pin "1") (pinfunction "1_1") (pintype "passive"))
      (node (ref "U3") (pin "4") (pinfunction "CAP-_4") (pintype "passive"))
    )
    (net (code "51") (name "Net-(U4-BOOT0)") (class "Default")
      (node (ref "R8") (pin "2") (pinfunction "2_2") (pintype "passive"))
      (node (ref "U4") (pin "44") (pinfunction "BOOT0_44") (pintype "input"))
    )
    (net (code "52") (name "Net-(U4-PB2{slash}BOOT1)") (class "Default")
      (node (ref "R2") (pin "1") (pinfunction "1_1") (pintype "passive"))
      (node (ref "U4") (pin "20") (pinfunction "PB2/BOOT1_20") (pintype "bidirectional"))
    )
    (net (code "53") (name "Net-(U6-QOUTA)") (class "Default")
      (node (ref "P2") (pin "1") (pintype "passive"))
      (node (ref "U6") (pin "14") (pinfunction "QOUTA_14") (pintype "passive"))
    )
    (net (code "54") (name "Net-(U6-Rset)") (class "Default")
      (node (ref "R7") (pin "2") (pinfunction "2_2") (pintype "passive"))
      (node (ref "U6") (pin "12") (pinfunction "Rset_12") (pintype "passive"))
    )
    (net (code "55") (name "Net-(U6-VINN)") (class "Default")
      (node (ref "RP1") (pin "3") (pinfunction "3_3") (pintype "passive"))
      (node (ref "U6") (pin "15") (pinfunction "VINN_15") (pintype "passive"))
    )
    (net (code "56") (name "VCC") (class "Default")
      (node (ref "C20") (pin "2") (pinfunction "2_2") (pintype "passive"))
      (node (ref "C21") (pin "2") (pinfunction "2_2") (pintype "passive"))
      (node (ref "R11") (pin "2") (pinfunction "2_2") (pintype "passive"))
      (node (ref "R2") (pin "2") (pinfunction "2_2") (pintype "passive"))
      (node (ref "U2") (pin "3") (pinfunction "LEDA_3") (pintype "passive"))
      (node (ref "U2") (pin "4") (pinfunction "VDD_4") (pintype "passive"))
      (node (ref "U4") (pin "24") (pinfunction "VDD_1_24") (pintype "power_in"))
      (node (ref "U4") (pin "36") (pinfunction "VDD_2_36") (pintype "power_in"))
      (node (ref "U4") (pin "48") (pinfunction "VDD_3_48") (pintype "power_in"))
      (node (ref "U4") (pin "9") (pinfunction "VDDA_9") (pintype "power_in"))
    )
    (net (code "57") (name "unconnected-(CR1-NC-Pad1)") (class "Default")
      (node (ref "CR1") (pin "1") (pinfunction "NC_1") (pintype "passive"))
    )
    (net (code "58") (name "unconnected-(S1-NO-Pad3)") (class "Default")
      (node (ref "S1") (pin "3") (pinfunction "NO_3") (pintype "passive"))
    )
    (net (code "59") (name "unconnected-(U1-NC-Pad4)") (class "Default")
      (node (ref "U1") (pin "4") (pinfunction "NC_4") (pintype "passive"))
    )
    (net (code "60") (name "unconnected-(U3-0SC-Pad7)") (class "Default")
      (node (ref "U3") (pin "7") (pinfunction "0SC_7") (pintype "passive"))
    )
    (net (code "61") (name "unconnected-(U3-NC-Pad1)") (class "Default")
      (node (ref "U3") (pin "1") (pinfunction "NC_1") (pintype "passive"))
    )
    (net (code "62") (name "unconnected-(U4-PA8-Pad29)") (class "Default")
      (node (ref "U4") (pin "29") (pinfunction "PA8_29") (pintype "bidirectional"))
    )
    (net (code "63") (name "unconnected-(U4-PA9-Pad30)") (class "Default")
      (node (ref "U4") (pin "30") (pinfunction "PA9_30") (pintype "bidirectional"))
    )
    (net (code "64") (name "unconnected-(U4-PA10-Pad31)") (class "Default")
      (node (ref "U4") (pin "31") (pinfunction "PA10_31") (pintype "bidirectional"))
    )
    (net (code "65") (name "unconnected-(U4-PA15{slash}JTDI-Pad38)") (class "Default")
      (node (ref "U4") (pin "38") (pinfunction "PA15/JTDI_38") (pintype "bidirectional"))
    )
    (net (code "66") (name "unconnected-(U4-PB3{slash}JTDO-Pad39)") (class "Default")
      (node (ref "U4") (pin "39") (pinfunction "PB3/JTDO_39") (pintype "bidirectional"))
    )
    (net (code "67") (name "unconnected-(U4-PB4{slash}JNTRST-Pad40)") (class "Default")
      (node (ref "U4") (pin "40") (pinfunction "PB4/JNTRST_40") (pintype "bidirectional"))
    )
    (net (code "68") (name "unconnected-(U4-PB11-Pad22)") (class "Default")
      (node (ref "U4") (pin "22") (pinfunction "PB11_22") (pintype "bidirectional"))
    )
    (net (code "69") (name "unconnected-(U4-PC13-TAMPER-RTC-Pad2)") (class "Default")
      (node (ref "U4") (pin "2") (pinfunction "PC13-TAMPER-RTC_2") (pintype "bidirectional"))
    )
    (net (code "70") (name "unconnected-(U4-PC14-OSC32_IN-Pad3)") (class "Default")
      (node (ref "U4") (pin "3") (pinfunction "PC14-OSC32_IN_3") (pintype "bidirectional"))
    )
    (net (code "71") (name "unconnected-(U4-PC15-OSC32_OUT-Pad4)") (class "Default")
      (node (ref "U4") (pin "4") (pinfunction "PC15-OSC32_OUT_4") (pintype "bidirectional"))
    )
    (net (code "72") (name "unconnected-(U4-VBAT-Pad1)") (class "Default")
      (node (ref "U4") (pin "1") (pinfunction "VBAT_1") (pintype "power_in"))
    )
    (net (code "73") (name "unconnected-(U6-DACBL-Pad17)") (class "Default")
      (node (ref "U6") (pin "17") (pinfunction "DACBL_17") (pintype "passive"))
    )
    (net (code "74") (name "unconnected-(U6-QOUTB-Pad13)") (class "Default")
      (node (ref "U6") (pin "13") (pinfunction "QOUTB_13") (pintype "passive"))
    )
    (net (code "75") (name "unconnected-(USB1-CC1-PadA5)") (class "Default")
      (node (ref "USB1") (pin "A5") (pinfunction "CC1_A5") (pintype "passive"))
    )
    (net (code "76") (name "unconnected-(USB1-CC2-PadB5)") (class "Default")
      (node (ref "USB1") (pin "B5") (pinfunction "CC2_B5") (pintype "passive"))
    )
    (net (code "77") (name "unconnected-(USB1-RX1+-PadB11)") (class "Default")
      (node (ref "USB1") (pin "B11") (pinfunction "RX1+_B11") (pintype "passive"))
    )
    (net (code "78") (name "unconnected-(USB1-RX1--PadB10)") (class "Default")
      (node (ref "USB1") (pin "B10") (pinfunction "RX1-_B10") (pintype "passive"))
    )
    (net (code "79") (name "unconnected-(USB1-RX2+-PadA11)") (class "Default")
      (node (ref "USB1") (pin "A11") (pinfunction "RX2+_A11") (pintype "passive"))
    )
    (net (code "80") (name "unconnected-(USB1-RX2--PadA10)") (class "Default")
      (node (ref "USB1") (pin "A10") (pinfunction "RX2-_A10") (pintype "passive"))
    )
    (net (code "81") (name "unconnected-(USB1-SBU1-PadA8)") (class "Default")
      (node (ref "USB1") (pin "A8") (pinfunction "SBU1_A8") (pintype "passive"))
    )
    (net (code "82") (name "unconnected-(USB1-SBU2-PadB8)") (class "Default")
      (node (ref "USB1") (pin "B8") (pinfunction "SBU2_B8") (pintype "passive"))
    )
    (net (code "83") (name "unconnected-(USB1-SH1-Pad1)") (class "Default")
      (node (ref "USB1") (pin "1") (pinfunction "SH1_1") (pintype "passive"))
    )
    (net (code "84") (name "unconnected-(USB1-SH2-Pad2)") (class "Default")
      (node (ref "USB1") (pin "2") (pinfunction "SH2_2") (pintype "passive"))
    )
    (net (code "85") (name "unconnected-(USB1-SH3-Pad3)") (class "Default")
      (node (ref "USB1") (pin "3") (pinfunction "SH3_3") (pintype "passive"))
    )
    (net (code "86") (name "unconnected-(USB1-SH4-Pad4)") (class "Default")
      (node (ref "USB1") (pin "4") (pinfunction "SH4_4") (pintype "passive"))
    )
    (net (code "87") (name "unconnected-(USB1-TX1+-PadA2)") (class "Default")
      (node (ref "USB1") (pin "A2") (pinfunction "TX1+_A2") (pintype "passive"))
    )
    (net (code "88") (name "unconnected-(USB1-TX1--PadA3)") (class "Default")
      (node (ref "USB1") (pin "A3") (pinfunction "TX1-_A3") (pintype "passive"))
    )
    (net (code "89") (name "unconnected-(USB1-TX2+-PadB2)") (class "Default")
      (node (ref "USB1") (pin "B2") (pinfunction "TX2+_B2") (pintype "passive"))
    )
    (net (code "90") (name "unconnected-(USB1-TX2--PadB3)") (class "Default")
      (node (ref "USB1") (pin "B3") (pinfunction "TX2-_B3") (pintype "passive"))
    )
  )
)
